# to_be_corrected.net
KiCad netlist of a schematic drawn in EAGLE
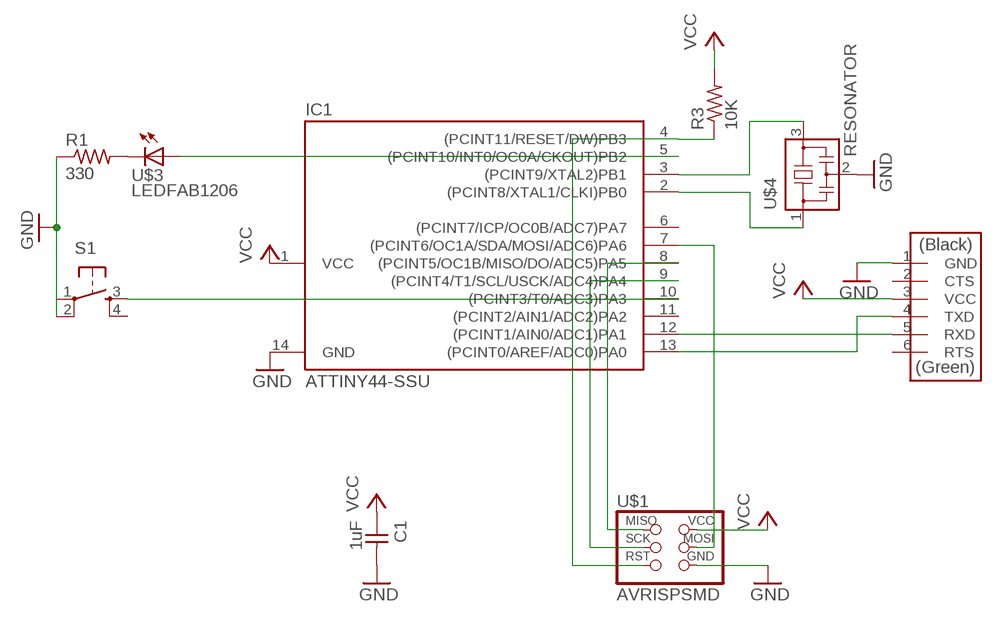
[diagram p0: schematic, sheet 1]

(export (version "E")
  (design (tool "Eeschema 10.0.6"))
  (components
    (comp (ref "C1")
      (value "1uF")
      (footprint "eagle-import:C1206FAB")
      (libsource (lib "eagle-import") (part "CAP-UNPOLARIZEDFAB"))
    )
    (comp (ref "IC1")
      (value "ATTINY44-SSU")
      (footprint "eagle-import:SOIC14")
      (libsource (lib "eagle-import") (part "ATTINY44-SSU"))
    )
    (comp (ref "R1")
      (value "330")
      (footprint "eagle-import:R1206FAB")
      (libsource (lib "eagle-import") (part "RES-US1206FAB"))
    )
    (comp (ref "R3")
      (value "10K")
      (footprint "eagle-import:R1206FAB")
      (libsource (lib "eagle-import") (part "RES-US1206FAB"))
    )
    (comp (ref "S1")
      (value "6MM_SWITCH6MM_SWITCH")
      (footprint "eagle-import:6MM_SWITCH")
      (libsource (lib "eagle-import") (part "6MM_SWITCH6MM_SWITCH"))
    )
    (comp (ref "U$1")
      (value "AVRISPSMD")
      (footprint "eagle-import:2X03SMD")
      (libsource (lib "eagle-import") (part "AVRISPSMD"))
    )
    (comp (ref "U$2")
      (value "FTDI-SMD-HEADER")
      (footprint "eagle-import:1X06SMD")
      (libsource (lib "eagle-import") (part "FTDI-SMD-HEADER"))
    )
    (comp (ref "U$3")
      (value "LEDFAB1206")
      (footprint "eagle-import:LED1206FAB")
      (libsource (lib "eagle-import") (part "LEDFAB1206"))
    )
    (comp (ref "U$4")
      (value "RESONATOR")
      (footprint "eagle-import:EFOBM")
      (libsource (lib "eagle-import") (part "RESONATOR"))
    )
  )
  (nets
    (net (code "1") (name "GND") (class "Default")
      (node (ref "C1") (pin "2") (pinfunction "2_2") (pintype "passive"))
      (node (ref "IC1") (pin "14") (pinfunction "GND_14") (pintype "power_in"))
      (node (ref "R1") (pin "1") (pinfunction "1_1") (pintype "passive"))
      (node (ref "S1") (pin "2") (pinfunction "P1_2") (pintype "passive"))
      (node (ref "U$1") (pin "6") (pinfunction "GND_6") (pintype "passive"))
      (node (ref "U$2") (pin "1") (pinfunction "GND_1") (pintype "bidirectional"))
      (node (ref "U$4") (pin "2") (pinfunction "2_2") (pintype "passive"))
    )
    (net (code "2") (name "Net-(IC1-(PCINT0{slash}AREF{slash}ADC0)PA0)") (class "Default")
      (node (ref "IC1") (pin "13") (pinfunction "(PCINT0/AREF/ADC0)PA0_13") (pintype "bidirectional"))
      (node (ref "U$2") (pin "4") (pinfunction "TXD_4") (pintype "bidirectional"))
    )
    (net (code "3") (name "Net-(IC1-(PCINT1{slash}AIN0{slash}ADC1)PA1)") (class "Default")
      (node (ref "IC1") (pin "12") (pinfunction "(PCINT1/AIN0/ADC1)PA1_12") (pintype "bidirectional"))
      (node (ref "U$2") (pin "5") (pinfunction "RXD_5") (pintype "bidirectional"))
    )
    (net (code "4") (name "Net-(IC1-(PCINT3{slash}T0{slash}ADC3)PA3)") (class "Default")
      (node (ref "IC1") (pin "10") (pinfunction "(PCINT3/T0/ADC3)PA3_10") (pintype "bidirectional"))
      (node (ref "S1") (pin "3") (pinfunction "S_3") (pintype "passive"))
    )
    (net (code "5") (name "Net-(IC1-(PCINT4{slash}T1{slash}SCL{slash}USCK{slash}ADC4)PA4)") (class "Default")
      (node (ref "IC1") (pin "9") (pinfunction "(PCINT4/T1/SCL/USCK/ADC4)PA4_9") (pintype "bidirectional"))
      (node (ref "U$1") (pin "3") (pinfunction "SCK_3") (pintype "passive"))
    )
    (net (code "6") (name "Net-(IC1-(PCINT5{slash}OC1B{slash}MISO{slash}DO{slash}ADC5)PA5)") (class "Default")
      (node (ref "IC1") (pin "8") (pinfunction "(PCINT5/OC1B/MISO/DO/ADC5)PA5_8") (pintype "bidirectional"))
      (node (ref "U$1") (pin "1") (pinfunction "MISO_1") (pintype "passive"))
    )
    (net (code "7") (name "Net-(IC1-(PCINT6{slash}OC1A{slash}SDA{slash}MOSI{slash}ADC6)PA6)") (class "Default")
      (node (ref "IC1") (pin "7") (pinfunction "(PCINT6/OC1A/SDA/MOSI/ADC6)PA6_7") (pintype "bidirectional"))
      (node (ref "U$1") (pin "4") (pinfunction "MOSI_4") (pintype "passive"))
    )
    (net (code "8") (name "Net-(IC1-(PCINT8{slash}XTAL1{slash}CLKI)PB0)") (class "Default")
      (node (ref "IC1") (pin "2") (pinfunction "(PCINT8/XTAL1/CLKI)PB0_2") (pintype "bidirectional"))
      (node (ref "U$4") (pin "1") (pinfunction "1_1") (pintype "passive"))
    )
    (net (code "9") (name "Net-(IC1-(PCINT9{slash}XTAL2)PB1)") (class "Default")
      (node (ref "IC1") (pin "3") (pinfunction "(PCINT9/XTAL2)PB1_3") (pintype "bidirectional"))
      (node (ref "U$4") (pin "3") (pinfunction "3_3") (pintype "passive"))
    )
    (net (code "10") (name "Net-(IC1-(PCINT10{slash}INT0{slash}OC0A{slash}CKOUT)PB2)") (class "Default")
      (node (ref "IC1") (pin "5") (pinfunction "(PCINT10/INT0/OC0A/CKOUT)PB2_5") (pintype "bidirectional"))
      (node (ref "U$3") (pin "1") (pinfunction "A_1") (pintype "passive"))
    )
    (net (code "11") (name "Net-(IC1-(PCINT11{slash}RESET{slash}DW)PB3)") (class "Default")
      (node (ref "IC1") (pin "4") (pinfunction "(PCINT11/RESET/DW)PB3_4") (pintype "bidirectional"))
      (node (ref "R3") (pin "1") (pinfunction "1_1") (pintype "passive"))
      (node (ref "U$1") (pin "5") (pinfunction "RST_5") (pintype "passive"))
    )
    (net (code "12") (name "Net-(U$3-C)") (class "Default")
      (node (ref "R1") (pin "2") (pinfunction "2_2") (pintype "passive"))
      (node (ref "U$3") (pin "2") (pinfunction "C_2") (pintype "passive"))
    )
    (net (code "13") (name "VCC") (class "Default")
      (node (ref "C1") (pin "1") (pinfunction "1_1") (pintype "passive"))
      (node (ref "IC1") (pin "1") (pinfunction "VCC_1") (pintype "power_in"))
      (node (ref "R3") (pin "2") (pinfunction "2_2") (pintype "passive"))
      (node (ref "U$1") (pin "2") (pinfunction "VCC_2") (pintype "passive"))
      (node (ref "U$2") (pin "3") (pinfunction "VCC_3") (pintype "bidirectional"))
    )
    (net (code "14") (name "unconnected-(IC1-(PCINT2{slash}AIN1{slash}ADC2)PA2-Pad11)") (class "Default")
      (node (ref "IC1") (pin "11") (pinfunction "(PCINT2/AIN1/ADC2)PA2_11") (pintype "bidirectional"))
    )
    (net (code "15") (name "unconnected-(IC1-(PCINT7{slash}ICP{slash}OC0B{slash}ADC7)PA7-Pad6)") (class "Default")
      (node (ref "IC1") (pin "6") (pinfunction "(PCINT7/ICP/OC0B/ADC7)PA7_6") (pintype "bidirectional"))
    )
    (net (code "16") (name "unconnected-(S1-P-Pad1)") (class "Default")
      (node (ref "S1") (pin "1") (pinfunction "P_1") (pintype "passive"))
    )
    (net (code "17") (name "unconnected-(S1-S1-Pad4)") (class "Default")
      (node (ref "S1") (pin "4") (pinfunction "S1_4") (pintype "passive"))
    )
    (net (code "18") (name "unconnected-(U$2-CTS-Pad2)") (class "Default")
      (node (ref "U$2") (pin "2") (pinfunction "CTS_2") (pintype "bidirectional"))
    )
    (net (code "19") (name "unconnected-(U$2-RTS-Pad6)") (class "Default")
      (node (ref "U$2") (pin "6") (pinfunction "RTS_6") (pintype "bidirectional"))
    )
  )
)
